# MgdOpl3.net
KiCad netlist of a schematic drawn in EAGLE
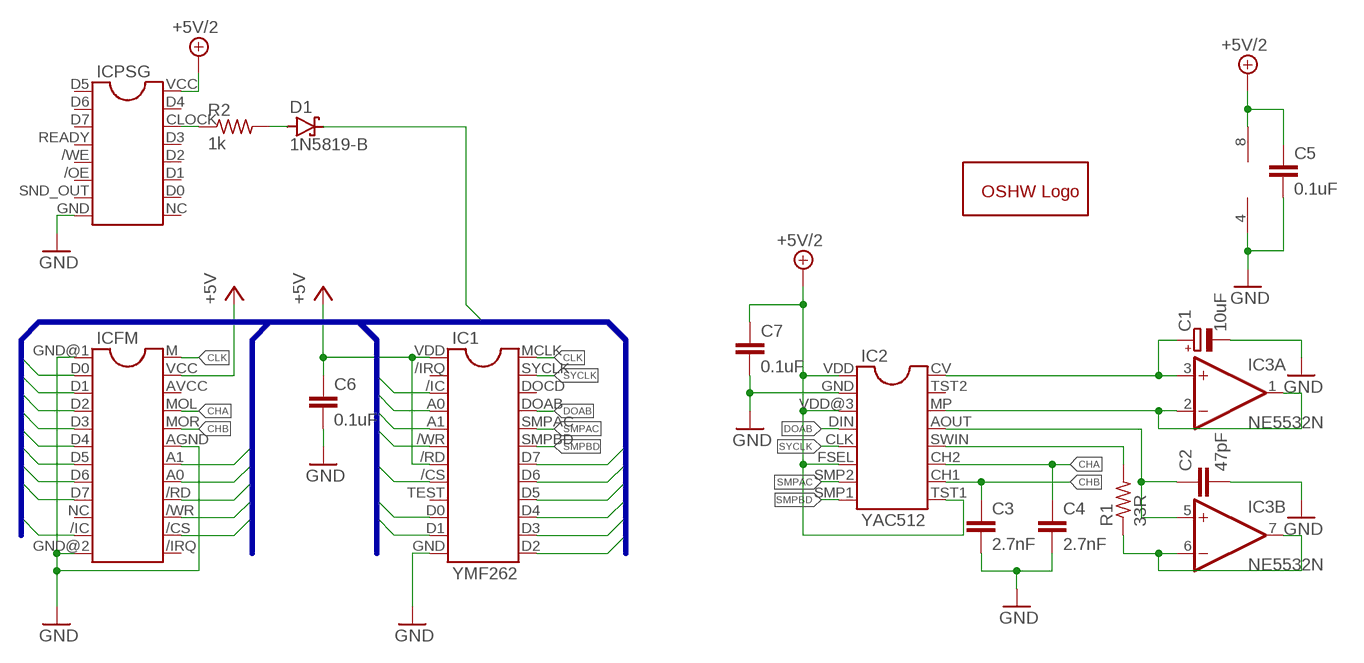
[diagram p0: schematic, sheet 1]

(export (version "E")
  (design (tool "Eeschema 10.0.6"))
  (components
    (comp (ref "C1")
      (value "10uF")
      (footprint "eagle-import:E2,5-5")
      (libsource (lib "eagle-import") (part "CPOL-EUE2.5-5"))
    )
    (comp (ref "C2")
      (value "47pF")
      (footprint "eagle-import:C025-024X044")
      (libsource (lib "eagle-import") (part "C-EU025-024X044"))
    )
    (comp (ref "C3")
      (value "2.7nF")
      (footprint "eagle-import:C025-024X044")
      (libsource (lib "eagle-import") (part "C-EU025-024X044"))
    )
    (comp (ref "C4")
      (value "2.7nF")
      (footprint "eagle-import:C025-024X044")
      (libsource (lib "eagle-import") (part "C-EU025-024X044"))
    )
    (comp (ref "C5")
      (value "0.1uF")
      (footprint "eagle-import:C025-024X044")
      (libsource (lib "eagle-import") (part "C-EU025-024X044"))
    )
    (comp (ref "C6")
      (value "0.1uF")
      (footprint "eagle-import:C025-024X044")
      (libsource (lib "eagle-import") (part "C-EU025-024X044"))
    )
    (comp (ref "C7")
      (value "0.1uF")
      (footprint "eagle-import:C025-024X044")
      (libsource (lib "eagle-import") (part "C-EU025-024X044"))
    )
    (comp (ref "D1")
      (value "1N5819-B")
      (footprint "eagle-import:DO41-7.6")
      (libsource (lib "eagle-import") (part "1N5819-B"))
    )
    (comp (ref "GOLD_ORB_SM2")
      (value "OSHWLOGOLOGO8MM")
      (footprint "eagle-import:OSHW_8MM")
      (libsource (lib "eagle-import") (part "OSHWLOGOLOGO8MM"))
    )
    (comp (ref "IC1")
      (value "YMF262")
      (footprint "eagle-import:YMF262")
      (libsource (lib "eagle-import") (part "YMF262"))
    )
    (comp (ref "IC2")
      (value "YAC512")
      (footprint "eagle-import:YAC512")
      (libsource (lib "eagle-import") (part "YAC512"))
    )
    (comp (ref "IC3")
      (value "NE5532N")
      (footprint "eagle-import:DIL08")
      (libsource (lib "eagle-import") (part "NE5532N"))
    )
    (comp (ref "ICFM")
      (value "YM2612YM2612_NOSILK")
      (footprint "eagle-import:YM2612_NOSILK")
      (libsource (lib "eagle-import") (part "YM2612YM2612_NOSILK"))
    )
    (comp (ref "ICPSG")
      (value "SN76489SN76489_NOSILK")
      (footprint "eagle-import:SN76489_NOSILK")
      (libsource (lib "eagle-import") (part "SN76489SN76489_NOSILK"))
    )
    (comp (ref "R1")
      (value "33R")
      (footprint "eagle-import:0204_7")
      (libsource (lib "eagle-import") (part "R-US_0204/7"))
    )
    (comp (ref "R2")
      (value "1k")
      (footprint "eagle-import:0204_7")
      (libsource (lib "eagle-import") (part "R-US_0204/7"))
    )
  )
  (nets
    (net (code "1") (name "+5V") (class "Default")
      (node (ref "C6") (pin "1") (pinfunction "1_1") (pintype "passive"))
      (node (ref "IC1") (pin "/RD") (pinfunction "/RD_/RD") (pintype "passive"))
      (node (ref "IC1") (pin "VDD") (pinfunction "VDD_VDD") (pintype "passive"))
      (node (ref "ICFM") (pin "VCC") (pinfunction "VCC_VCC") (pintype "passive"))
    )
    (net (code "2") (name "+5V{slash}2") (class "Default")
      (node (ref "C5") (pin "1") (pinfunction "1_1") (pintype "passive"))
      (node (ref "C7") (pin "1") (pinfunction "1_1") (pintype "passive"))
      (node (ref "IC2") (pin "FSEL") (pinfunction "FSEL_FSEL") (pintype "passive"))
      (node (ref "IC2") (pin "TST1") (pinfunction "TST1_TST1") (pintype "passive"))
      (node (ref "IC2") (pin "VDD") (pinfunction "VDD_VDD") (pintype "passive"))
      (node (ref "IC2") (pin "VDD@3") (pinfunction "VDD_VDD@3") (pintype "passive"))
      (node (ref "IC3") (pin "8") (pinfunction "V+_8") (pintype "power_in"))
      (node (ref "ICPSG") (pin "VCC") (pinfunction "VCC_VCC") (pintype "passive"))
    )
    (net (code "3") (name "/A0") (class "Default")
      (node (ref "IC1") (pin "A0") (pinfunction "A0_A0") (pintype "passive"))
      (node (ref "ICFM") (pin "A0") (pinfunction "A0_A0") (pintype "passive"))
    )
    (net (code "4") (name "/A1") (class "Default")
      (node (ref "IC1") (pin "A1") (pinfunction "A1_A1") (pintype "passive"))
      (node (ref "ICFM") (pin "A1") (pinfunction "A1_A1") (pintype "passive"))
    )
    (net (code "5") (name "/D0") (class "Default")
      (node (ref "IC1") (pin "D0") (pinfunction "D0_D0") (pintype "passive"))
      (node (ref "ICFM") (pin "D0") (pinfunction "D0_D0") (pintype "passive"))
    )
    (net (code "6") (name "/D1") (class "Default")
      (node (ref "IC1") (pin "D1") (pinfunction "D1_D1") (pintype "passive"))
      (node (ref "ICFM") (pin "D1") (pinfunction "D1_D1") (pintype "passive"))
    )
    (net (code "7") (name "/D2") (class "Default")
      (node (ref "IC1") (pin "D2") (pinfunction "D2_D2") (pintype "passive"))
      (node (ref "ICFM") (pin "D2") (pinfunction "D2_D2") (pintype "passive"))
    )
    (net (code "8") (name "/D3") (class "Default")
      (node (ref "D1") (pin "C") (pinfunction "C_C") (pintype "passive"))
      (node (ref "IC1") (pin "D3") (pinfunction "D3_D3") (pintype "passive"))
      (node (ref "ICFM") (pin "D3") (pinfunction "D3_D3") (pintype "passive"))
    )
    (net (code "9") (name "/D4") (class "Default")
      (node (ref "IC1") (pin "D4") (pinfunction "D4_D4") (pintype "passive"))
      (node (ref "ICFM") (pin "D4") (pinfunction "D4_D4") (pintype "passive"))
    )
    (net (code "10") (name "/D5") (class "Default")
      (node (ref "IC1") (pin "D5") (pinfunction "D5_D5") (pintype "passive"))
      (node (ref "ICFM") (pin "D5") (pinfunction "D5_D5") (pintype "passive"))
    )
    (net (code "11") (name "/D6") (class "Default")
      (node (ref "IC1") (pin "D6") (pinfunction "D6_D6") (pintype "passive"))
      (node (ref "ICFM") (pin "D6") (pinfunction "D6_D6") (pintype "passive"))
    )
    (net (code "12") (name "/D7") (class "Default")
      (node (ref "IC1") (pin "D7") (pinfunction "D7_D7") (pintype "passive"))
      (node (ref "ICFM") (pin "D7") (pinfunction "D7_D7") (pintype "passive"))
    )
    (net (code "13") (name "/{slash}CS") (class "Default")
      (node (ref "IC1") (pin "/CS") (pinfunction "/CS_/CS") (pintype "passive"))
      (node (ref "ICFM") (pin "/CS") (pinfunction "/CS_/CS") (pintype "passive"))
    )
    (net (code "14") (name "/{slash}IC") (class "Default")
      (node (ref "IC1") (pin "/IC") (pinfunction "/IC_/IC") (pintype "passive"))
      (node (ref "ICFM") (pin "/IC") (pinfunction "/IC_/IC") (pintype "passive"))
    )
    (net (code "15") (name "/{slash}WR") (class "Default")
      (node (ref "IC1") (pin "/WR") (pinfunction "/WR_/WR") (pintype "passive"))
      (node (ref "ICFM") (pin "/WR") (pinfunction "/WR_/WR") (pintype "passive"))
    )
    (net (code "16") (name "CHA") (class "Default")
      (node (ref "C4") (pin "1") (pinfunction "1_1") (pintype "passive"))
      (node (ref "IC2") (pin "CH2") (pinfunction "CH2_CH2") (pintype "passive"))
      (node (ref "ICFM") (pin "MOL") (pinfunction "MOL_MOL") (pintype "passive"))
    )
    (net (code "17") (name "CHB") (class "Default")
      (node (ref "C3") (pin "1") (pinfunction "1_1") (pintype "passive"))
      (node (ref "IC2") (pin "CH1") (pinfunction "CH1_CH1") (pintype "passive"))
      (node (ref "ICFM") (pin "MOR") (pinfunction "MOR_MOR") (pintype "passive"))
    )
    (net (code "18") (name "CLK") (class "Default")
      (node (ref "IC1") (pin "MCLK") (pinfunction "MCLK_MCLK") (pintype "passive"))
      (node (ref "ICFM") (pin "M") (pinfunction "M_M") (pintype "passive"))
    )
    (net (code "19") (name "DOAB") (class "Default")
      (node (ref "IC1") (pin "DOAB") (pinfunction "DOAB_DOAB") (pintype "passive"))
      (node (ref "IC2") (pin "DIN") (pinfunction "DIN_DIN") (pintype "passive"))
    )
    (net (code "20") (name "GND") (class "Default")
      (node (ref "C1") (pin "-") (pinfunction "-_-") (pintype "passive"))
      (node (ref "C2") (pin "2") (pinfunction "2_2") (pintype "passive"))
      (node (ref "C3") (pin "2") (pinfunction "2_2") (pintype "passive"))
      (node (ref "C4") (pin "2") (pinfunction "2_2") (pintype "passive"))
      (node (ref "C5") (pin "2") (pinfunction "2_2") (pintype "passive"))
      (node (ref "C6") (pin "2") (pinfunction "2_2") (pintype "passive"))
      (node (ref "C7") (pin "2") (pinfunction "2_2") (pintype "passive"))
      (node (ref "IC1") (pin "GND") (pinfunction "GND_GND") (pintype "passive"))
      (node (ref "IC2") (pin "GND") (pinfunction "GND_GND") (pintype "passive"))
      (node (ref "IC3") (pin "4") (pinfunction "V-_4") (pintype "power_in"))
      (node (ref "ICFM") (pin "AGND") (pinfunction "AGND_AGND") (pintype "passive"))
      (node (ref "ICFM") (pin "GND@1") (pinfunction "GND_GND@1") (pintype "passive"))
      (node (ref "ICFM") (pin "GND@2") (pinfunction "GND_GND@2") (pintype "passive"))
      (node (ref "ICPSG") (pin "GND") (pinfunction "GND_GND") (pintype "passive"))
    )
    (net (code "21") (name "Net-(D1-PadA)") (class "Default")
      (node (ref "D1") (pin "A") (pinfunction "A_A") (pintype "passive"))
      (node (ref "R2") (pin "2") (pinfunction "2_2") (pintype "passive"))
    )
    (net (code "22") (name "Net-(IC2-PadSWIN)") (class "Default")
      (node (ref "IC2") (pin "SWIN") (pinfunction "SWIN_SWIN") (pintype "passive"))
      (node (ref "R1") (pin "2") (pinfunction "2_2") (pintype "passive"))
    )
    (net (code "23") (name "Net-(IC3A-+IN)") (class "Default")
      (node (ref "C1") (pin "+") (pinfunction "+_+") (pintype "passive"))
      (node (ref "IC2") (pin "CV") (pinfunction "CV_CV") (pintype "passive"))
      (node (ref "IC3") (pin "3") (pinfunction "+IN_3") (pintype "input"))
    )
    (net (code "24") (name "Net-(IC3A--IN)") (class "Default")
      (node (ref "IC2") (pin "MP") (pinfunction "MP_MP") (pintype "passive"))
      (node (ref "IC3") (pin "1") (pinfunction "OUT_1") (pintype "output"))
      (node (ref "IC3") (pin "2") (pinfunction "-IN_2") (pintype "input"))
    )
    (net (code "25") (name "Net-(IC3B-+IN)") (class "Default")
      (node (ref "C2") (pin "1") (pinfunction "1_1") (pintype "passive"))
      (node (ref "IC2") (pin "AOUT") (pinfunction "AOUT_AOUT") (pintype "passive"))
      (node (ref "IC3") (pin "5") (pinfunction "+IN_5") (pintype "input"))
    )
    (net (code "26") (name "Net-(IC3B--IN)") (class "Default")
      (node (ref "IC3") (pin "6") (pinfunction "-IN_6") (pintype "input"))
      (node (ref "IC3") (pin "7") (pinfunction "OUT_7") (pintype "output"))
      (node (ref "R1") (pin "1") (pinfunction "1_1") (pintype "passive"))
    )
    (net (code "27") (name "Net-(ICPSG-PadCLOCK)") (class "Default")
      (node (ref "ICPSG") (pin "CLOCK") (pinfunction "CLOCK_CLOCK") (pintype "passive"))
      (node (ref "R2") (pin "1") (pinfunction "1_1") (pintype "passive"))
    )
    (net (code "28") (name "SMPAC") (class "Default")
      (node (ref "IC1") (pin "SMPAC") (pinfunction "SMPAC_SMPAC") (pintype "passive"))
      (node (ref "IC2") (pin "SMP2") (pinfunction "SMP2_SMP2") (pintype "passive"))
    )
    (net (code "29") (name "SMPBD") (class "Default")
      (node (ref "IC1") (pin "SMPBD") (pinfunction "SMPBD_SMPBD") (pintype "passive"))
      (node (ref "IC2") (pin "SMP1") (pinfunction "SMP1_SMP1") (pintype "passive"))
    )
    (net (code "30") (name "SYCLK") (class "Default")
      (node (ref "IC1") (pin "SYCLK") (pinfunction "SYCLK_SYCLK") (pintype "passive"))
      (node (ref "IC2") (pin "CLK") (pinfunction "CLK_CLK") (pintype "passive"))
    )
    (net (code "31") (name "unconnected-(IC1-PadDOCD)") (class "Default")
      (node (ref "IC1") (pin "DOCD") (pinfunction "DOCD_DOCD") (pintype "passive"))
    )
    (net (code "32") (name "unconnected-(IC1-PadTEST)") (class "Default")
      (node (ref "IC1") (pin "TEST") (pinfunction "TEST_TEST") (pintype "passive"))
    )
    (net (code "33") (name "unconnected-(IC1-Pad{slash}IRQ)") (class "Default")
      (node (ref "IC1") (pin "/IRQ") (pinfunction "/IRQ_/IRQ") (pintype "passive"))
    )
    (net (code "34") (name "unconnected-(IC2-PadTST2)") (class "Default")
      (node (ref "IC2") (pin "TST2") (pinfunction "TST2_TST2") (pintype "passive"))
    )
    (net (code "35") (name "unconnected-(ICFM-PadAVCC)") (class "Default")
      (node (ref "ICFM") (pin "AVCC") (pinfunction "AVCC_AVCC") (pintype "passive"))
    )
    (net (code "36") (name "unconnected-(ICFM-PadNC)") (class "Default")
      (node (ref "ICFM") (pin "NC") (pinfunction "NC_NC") (pintype "passive"))
    )
    (net (code "37") (name "unconnected-(ICFM-Pad{slash}IRQ)") (class "Default")
      (node (ref "ICFM") (pin "/IRQ") (pinfunction "/IRQ_/IRQ") (pintype "passive"))
    )
    (net (code "38") (name "unconnected-(ICFM-Pad{slash}RD)") (class "Default")
      (node (ref "ICFM") (pin "/RD") (pinfunction "/RD_/RD") (pintype "passive"))
    )
    (net (code "39") (name "unconnected-(ICPSG-PadD0)") (class "Default")
      (node (ref "ICPSG") (pin "D0") (pinfunction "D0_D0") (pintype "passive"))
    )
    (net (code "40") (name "unconnected-(ICPSG-PadD1)") (class "Default")
      (node (ref "ICPSG") (pin "D1") (pinfunction "D1_D1") (pintype "passive"))
    )
    (net (code "41") (name "unconnected-(ICPSG-PadD2)") (class "Default")
      (node (ref "ICPSG") (pin "D2") (pinfunction "D2_D2") (pintype "passive"))
    )
    (net (code "42") (name "unconnected-(ICPSG-PadD3)") (class "Default")
      (node (ref "ICPSG") (pin "D3") (pinfunction "D3_D3") (pintype "passive"))
    )
    (net (code "43") (name "unconnected-(ICPSG-PadD4)") (class "Default")
      (node (ref "ICPSG") (pin "D4") (pinfunction "D4_D4") (pintype "passive"))
    )
    (net (code "44") (name "unconnected-(ICPSG-PadD5)") (class "Default")
      (node (ref "ICPSG") (pin "D5") (pinfunction "D5_D5") (pintype "passive"))
    )
    (net (code "45") (name "unconnected-(ICPSG-PadD6)") (class "Default")
      (node (ref "ICPSG") (pin "D6") (pinfunction "D6_D6") (pintype "passive"))
    )
    (net (code "46") (name "unconnected-(ICPSG-PadD7)") (class "Default")
      (node (ref "ICPSG") (pin "D7") (pinfunction "D7_D7") (pintype "passive"))
    )
    (net (code "47") (name "unconnected-(ICPSG-PadNC)") (class "Default")
      (node (ref "ICPSG") (pin "NC") (pinfunction "NC_NC") (pintype "passive"))
    )
    (net (code "48") (name "unconnected-(ICPSG-PadREADY)") (class "Default")
      (node (ref "ICPSG") (pin "READY") (pinfunction "READY_READY") (pintype "passive"))
    )
    (net (code "49") (name "unconnected-(ICPSG-PadSND_OUT)") (class "Default")
      (node (ref "ICPSG") (pin "SND_OUT") (pinfunction "SND_OUT_SND_OUT") (pintype "passive"))
    )
    (net (code "50") (name "unconnected-(ICPSG-Pad{slash}OE)") (class "Default")
      (node (ref "ICPSG") (pin "/OE") (pinfunction "/OE_/OE") (pintype "passive"))
    )
    (net (code "51") (name "unconnected-(ICPSG-Pad{slash}WE)") (class "Default")
      (node (ref "ICPSG") (pin "/WE") (pinfunction "/WE_/WE") (pintype "passive"))
    )
  )
)
